# Connectors.net
KiCad netlist of a schematic drawn in Altium Designer
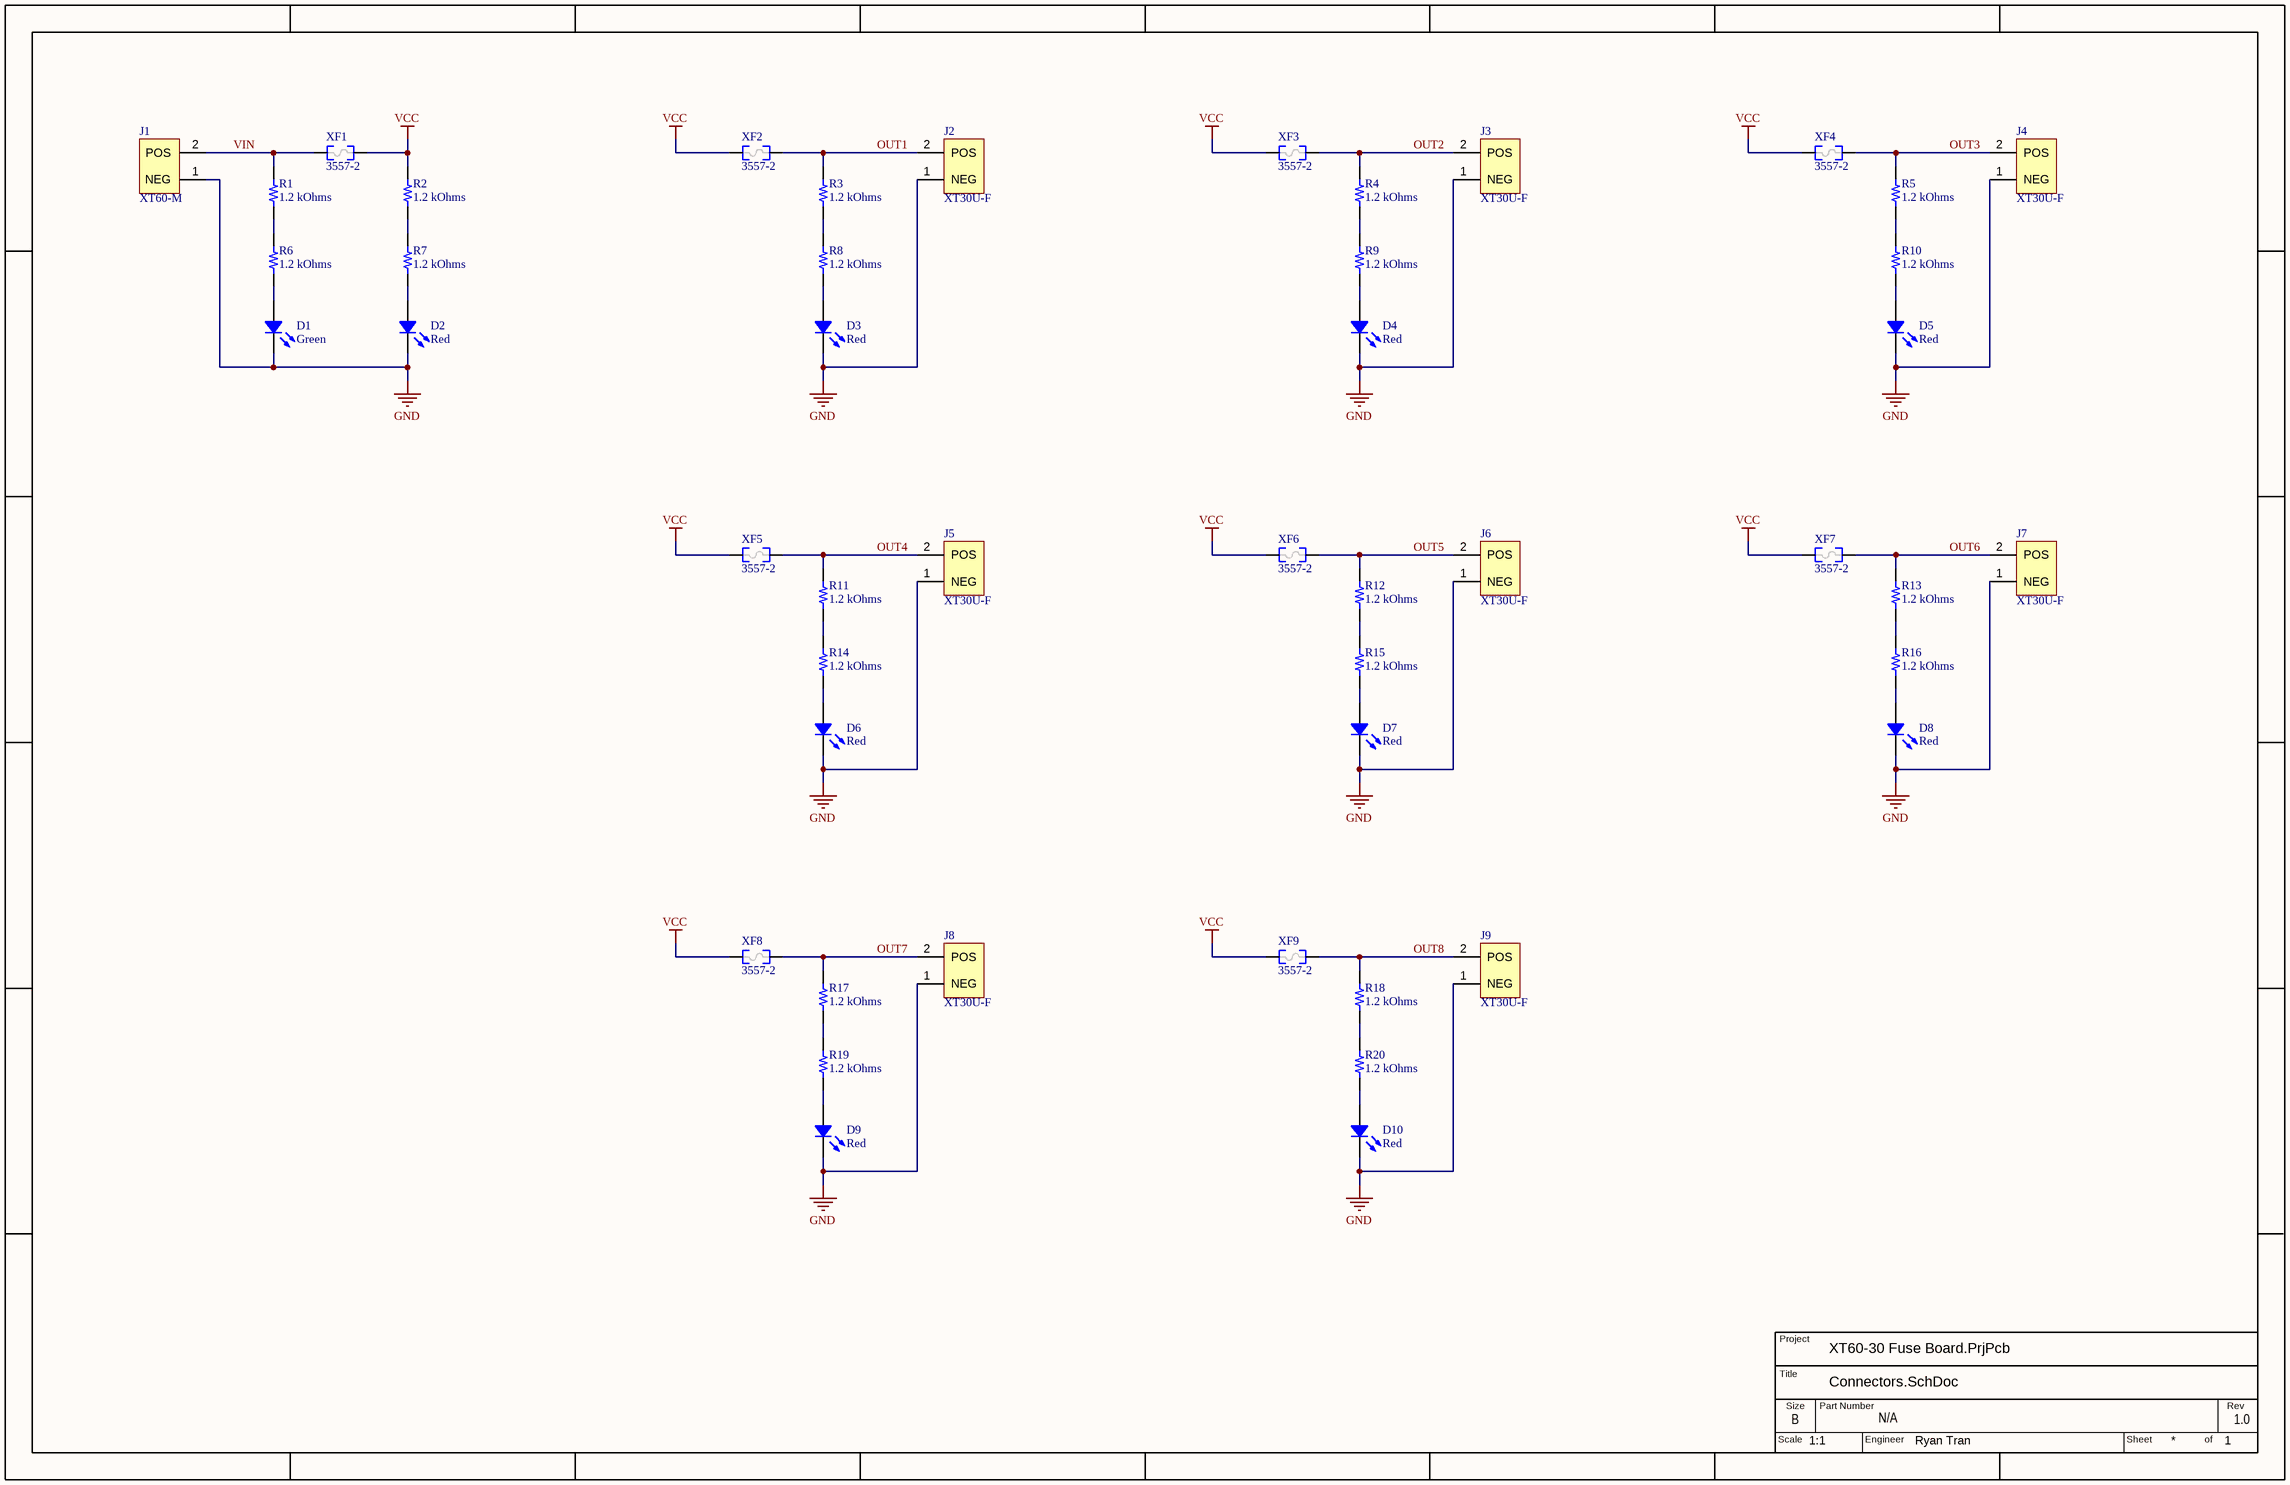
[diagram p0: Connectors.SchDoc]

(export (version "E")
  (design (tool "Eeschema 10.0.6"))
  (components
    (comp (ref "D1")
      (value "Green")
      (footprint "LED 0603_1608 GREEN")
      (description "LED GREEN CLEAR CHIP SMD")
      (fields (field (name "PART NUMBER") "LTST-C193TGKT-5A") (field (name "MANUFACTURER") "Lite-On Inc."))
      (libsource (lib "Celestial Altium Library - altium_library") (part "LED"))
    )
    (comp (ref "D2")
      (value "Red")
      (footprint "LED 0603_1608 RED")
      (description "LED RED CLEAR 2SMD")
      (fields
        (field (name "PART NUMBER") "19-217/R6C-AL1M2VY/3T")
        (field (name "MANUFACTURER") "Everlight Electronics Co Ltd")
      )
      (libsource (lib "Celestial Altium Library - altium_library") (part "LED"))
    )
    (comp (ref "D3")
      (value "Red")
      (footprint "LED 0603_1608 RED")
      (description "LED RED CLEAR 2SMD")
      (fields
        (field (name "PART NUMBER") "19-217/R6C-AL1M2VY/3T")
        (field (name "MANUFACTURER") "Everlight Electronics Co Ltd")
      )
      (libsource (lib "Celestial Altium Library - altium_library") (part "LED"))
    )
    (comp (ref "D4")
      (value "Red")
      (footprint "LED 0603_1608 RED")
      (description "LED RED CLEAR 2SMD")
      (fields
        (field (name "PART NUMBER") "19-217/R6C-AL1M2VY/3T")
        (field (name "MANUFACTURER") "Everlight Electronics Co Ltd")
      )
      (libsource (lib "Celestial Altium Library - altium_library") (part "LED"))
    )
    (comp (ref "D5")
      (value "Red")
      (footprint "LED 0603_1608 RED")
      (description "LED RED CLEAR 2SMD")
      (fields
        (field (name "PART NUMBER") "19-217/R6C-AL1M2VY/3T")
        (field (name "MANUFACTURER") "Everlight Electronics Co Ltd")
      )
      (libsource (lib "Celestial Altium Library - altium_library") (part "LED"))
    )
    (comp (ref "D6")
      (value "Red")
      (footprint "LED 0603_1608 RED")
      (description "LED RED CLEAR 2SMD")
      (fields
        (field (name "PART NUMBER") "19-217/R6C-AL1M2VY/3T")
        (field (name "MANUFACTURER") "Everlight Electronics Co Ltd")
      )
      (libsource (lib "Celestial Altium Library - altium_library") (part "LED"))
    )
    (comp (ref "D7")
      (value "Red")
      (footprint "LED 0603_1608 RED")
      (description "LED RED CLEAR 2SMD")
      (fields
        (field (name "PART NUMBER") "19-217/R6C-AL1M2VY/3T")
        (field (name "MANUFACTURER") "Everlight Electronics Co Ltd")
      )
      (libsource (lib "Celestial Altium Library - altium_library") (part "LED"))
    )
    (comp (ref "D8")
      (value "Red")
      (footprint "LED 0603_1608 RED")
      (description "LED RED CLEAR 2SMD")
      (fields
        (field (name "PART NUMBER") "19-217/R6C-AL1M2VY/3T")
        (field (name "MANUFACTURER") "Everlight Electronics Co Ltd")
      )
      (libsource (lib "Celestial Altium Library - altium_library") (part "LED"))
    )
    (comp (ref "D9")
      (value "Red")
      (footprint "LED 0603_1608 RED")
      (description "LED RED CLEAR 2SMD")
      (fields
        (field (name "PART NUMBER") "19-217/R6C-AL1M2VY/3T")
        (field (name "MANUFACTURER") "Everlight Electronics Co Ltd")
      )
      (libsource (lib "Celestial Altium Library - altium_library") (part "LED"))
    )
    (comp (ref "D10")
      (value "Red")
      (footprint "LED 0603_1608 RED")
      (description "LED RED CLEAR 2SMD")
      (fields
        (field (name "PART NUMBER") "19-217/R6C-AL1M2VY/3T")
        (field (name "MANUFACTURER") "Everlight Electronics Co Ltd")
      )
      (libsource (lib "Celestial Altium Library - altium_library") (part "LED"))
    )
    (comp (ref "J1")
      (value "XT60-M")
      (footprint "AMASS_XT60-M")
      (description "Plug; DC supply; XT60; male; PIN: 2; for cable; soldered; 30A; 500V")
      (fields (field (name "MF") "AMASS"))
      (libsource (lib "XT60-30_Fuse_Board_Symbols") (part "XT60-M"))
    )
    (comp (ref "J2")
      (value "XT30U-F")
      (footprint "AMASS_XT30-M")
      (description "Plug; DC supply; XT30; female; PIN: 2; for cable; soldering; 15A")
      (fields (field (name "MP") "XT60-M") (field (name "MF") "AMASS"))
      (libsource (lib "XT60-30_Fuse_Board_Symbols") (part "XT30U-F"))
    )
    (comp (ref "J3")
      (value "XT30U-F")
      (footprint "AMASS_XT30-M")
      (description "Plug; DC supply; XT30; female; PIN: 2; for cable; soldering; 15A")
      (fields (field (name "MP") "XT60-M") (field (name "MF") "AMASS"))
      (libsource (lib "XT60-30_Fuse_Board_Symbols") (part "XT30U-F"))
    )
    (comp (ref "J4")
      (value "XT30U-F")
      (footprint "AMASS_XT30-M")
      (description "Plug; DC supply; XT30; female; PIN: 2; for cable; soldering; 15A")
      (fields (field (name "MP") "XT60-M") (field (name "MF") "AMASS"))
      (libsource (lib "XT60-30_Fuse_Board_Symbols") (part "XT30U-F"))
    )
    (comp (ref "J5")
      (value "XT30U-F")
      (footprint "AMASS_XT30-M")
      (description "Plug; DC supply; XT30; female; PIN: 2; for cable; soldering; 15A")
      (fields (field (name "MP") "XT60-M") (field (name "MF") "AMASS"))
      (libsource (lib "XT60-30_Fuse_Board_Symbols") (part "XT30U-F"))
    )
    (comp (ref "J6")
      (value "XT30U-F")
      (footprint "AMASS_XT30-M")
      (description "Plug; DC supply; XT30; female; PIN: 2; for cable; soldering; 15A")
      (fields (field (name "MP") "XT60-M") (field (name "MF") "AMASS"))
      (libsource (lib "XT60-30_Fuse_Board_Symbols") (part "XT30U-F"))
    )
    (comp (ref "J7")
      (value "XT30U-F")
      (footprint "AMASS_XT30-M")
      (description "Plug; DC supply; XT30; female; PIN: 2; for cable; soldering; 15A")
      (fields (field (name "MP") "XT60-M") (field (name "MF") "AMASS"))
      (libsource (lib "XT60-30_Fuse_Board_Symbols") (part "XT30U-F"))
    )
    (comp (ref "J8")
      (value "XT30U-F")
      (footprint "AMASS_XT30-M")
      (description "Plug; DC supply; XT30; female; PIN: 2; for cable; soldering; 15A")
      (fields (field (name "MP") "XT60-M") (field (name "MF") "AMASS"))
      (libsource (lib "XT60-30_Fuse_Board_Symbols") (part "XT30U-F"))
    )
    (comp (ref "J9")
      (value "XT30U-F")
      (footprint "AMASS_XT30-M")
      (description "Plug; DC supply; XT30; female; PIN: 2; for cable; soldering; 15A")
      (fields (field (name "MP") "XT60-M") (field (name "MF") "AMASS"))
      (libsource (lib "XT60-30_Fuse_Board_Symbols") (part "XT30U-F"))
    )
    (comp (ref "R1")
      (value "1.2 kOhms")
      (footprint "RES 1210_3225")
      (description "RES SMD 1.2K OHM 5% 1/2W 1210")
      (fields
        (field (name "PART NUMBER") "ERJ-14YJ122U")
        (field (name "MANUFACTURER") "Panasonic Electronic Components")
      )
      (libsource (lib "Celestial Altium Library - altium_library") (part "Resistor"))
    )
    (comp (ref "R2")
      (value "1.2 kOhms")
      (footprint "RES 1210_3225")
      (description "RES SMD 1.2K OHM 5% 1/2W 1210")
      (fields
        (field (name "PART NUMBER") "ERJ-14YJ122U")
        (field (name "MANUFACTURER") "Panasonic Electronic Components")
      )
      (libsource (lib "Celestial Altium Library - altium_library") (part "Resistor"))
    )
    (comp (ref "R3")
      (value "1.2 kOhms")
      (footprint "RES 1210_3225")
      (description "RES SMD 1.2K OHM 5% 1/2W 1210")
      (fields
        (field (name "PART NUMBER") "ERJ-14YJ122U")
        (field (name "MANUFACTURER") "Panasonic Electronic Components")
      )
      (libsource (lib "Celestial Altium Library - altium_library") (part "Resistor"))
    )
    (comp (ref "R4")
      (value "1.2 kOhms")
      (footprint "RES 1210_3225")
      (description "RES SMD 1.2K OHM 5% 1/2W 1210")
      (fields
        (field (name "PART NUMBER") "ERJ-14YJ122U")
        (field (name "MANUFACTURER") "Panasonic Electronic Components")
      )
      (libsource (lib "Celestial Altium Library - altium_library") (part "Resistor"))
    )
    (comp (ref "R5")
      (value "1.2 kOhms")
      (footprint "RES 1210_3225")
      (description "RES SMD 1.2K OHM 5% 1/2W 1210")
      (fields
        (field (name "PART NUMBER") "ERJ-14YJ122U")
        (field (name "MANUFACTURER") "Panasonic Electronic Components")
      )
      (libsource (lib "Celestial Altium Library - altium_library") (part "Resistor"))
    )
    (comp (ref "R6")
      (value "1.2 kOhms")
      (footprint "RES 1210_3225")
      (description "RES SMD 1.2K OHM 5% 1/2W 1210")
      (fields
        (field (name "PART NUMBER") "ERJ-14YJ122U")
        (field (name "MANUFACTURER") "Panasonic Electronic Components")
      )
      (libsource (lib "Celestial Altium Library - altium_library") (part "Resistor"))
    )
    (comp (ref "R7")
      (value "1.2 kOhms")
      (footprint "RES 1210_3225")
      (description "RES SMD 1.2K OHM 5% 1/2W 1210")
      (fields
        (field (name "PART NUMBER") "ERJ-14YJ122U")
        (field (name "MANUFACTURER") "Panasonic Electronic Components")
      )
      (libsource (lib "Celestial Altium Library - altium_library") (part "Resistor"))
    )
    (comp (ref "R8")
      (value "1.2 kOhms")
      (footprint "RES 1210_3225")
      (description "RES SMD 1.2K OHM 5% 1/2W 1210")
      (fields
        (field (name "PART NUMBER") "ERJ-14YJ122U")
        (field (name "MANUFACTURER") "Panasonic Electronic Components")
      )
      (libsource (lib "Celestial Altium Library - altium_library") (part "Resistor"))
    )
    (comp (ref "R9")
      (value "1.2 kOhms")
      (footprint "RES 1210_3225")
      (description "RES SMD 1.2K OHM 5% 1/2W 1210")
      (fields
        (field (name "PART NUMBER") "ERJ-14YJ122U")
        (field (name "MANUFACTURER") "Panasonic Electronic Components")
      )
      (libsource (lib "Celestial Altium Library - altium_library") (part "Resistor"))
    )
    (comp (ref "R10")
      (value "1.2 kOhms")
      (footprint "RES 1210_3225")
      (description "RES SMD 1.2K OHM 5% 1/2W 1210")
      (fields
        (field (name "PART NUMBER") "ERJ-14YJ122U")
        (field (name "MANUFACTURER") "Panasonic Electronic Components")
      )
      (libsource (lib "Celestial Altium Library - altium_library") (part "Resistor"))
    )
    (comp (ref "R11")
      (value "1.2 kOhms")
      (footprint "RES 1210_3225")
      (description "RES SMD 1.2K OHM 5% 1/2W 1210")
      (fields
        (field (name "PART NUMBER") "ERJ-14YJ122U")
        (field (name "MANUFACTURER") "Panasonic Electronic Components")
      )
      (libsource (lib "Celestial Altium Library - altium_library") (part "Resistor"))
    )
    (comp (ref "R12")
      (value "1.2 kOhms")
      (footprint "RES 1210_3225")
      (description "RES SMD 1.2K OHM 5% 1/2W 1210")
      (fields
        (field (name "PART NUMBER") "ERJ-14YJ122U")
        (field (name "MANUFACTURER") "Panasonic Electronic Components")
      )
      (libsource (lib "Celestial Altium Library - altium_library") (part "Resistor"))
    )
    (comp (ref "R13")
      (value "1.2 kOhms")
      (footprint "RES 1210_3225")
      (description "RES SMD 1.2K OHM 5% 1/2W 1210")
      (fields
        (field (name "PART NUMBER") "ERJ-14YJ122U")
        (field (name "MANUFACTURER") "Panasonic Electronic Components")
      )
      (libsource (lib "Celestial Altium Library - altium_library") (part "Resistor"))
    )
    (comp (ref "R14")
      (value "1.2 kOhms")
      (footprint "RES 1210_3225")
      (description "RES SMD 1.2K OHM 5% 1/2W 1210")
      (fields
        (field (name "PART NUMBER") "ERJ-14YJ122U")
        (field (name "MANUFACTURER") "Panasonic Electronic Components")
      )
      (libsource (lib "Celestial Altium Library - altium_library") (part "Resistor"))
    )
    (comp (ref "R15")
      (value "1.2 kOhms")
      (footprint "RES 1210_3225")
      (description "RES SMD 1.2K OHM 5% 1/2W 1210")
      (fields
        (field (name "PART NUMBER") "ERJ-14YJ122U")
        (field (name "MANUFACTURER") "Panasonic Electronic Components")
      )
      (libsource (lib "Celestial Altium Library - altium_library") (part "Resistor"))
    )
    (comp (ref "R16")
      (value "1.2 kOhms")
      (footprint "RES 1210_3225")
      (description "RES SMD 1.2K OHM 5% 1/2W 1210")
      (fields
        (field (name "PART NUMBER") "ERJ-14YJ122U")
        (field (name "MANUFACTURER") "Panasonic Electronic Components")
      )
      (libsource (lib "Celestial Altium Library - altium_library") (part "Resistor"))
    )
    (comp (ref "R17")
      (value "1.2 kOhms")
      (footprint "RES 1210_3225")
      (description "RES SMD 1.2K OHM 5% 1/2W 1210")
      (fields
        (field (name "PART NUMBER") "ERJ-14YJ122U")
        (field (name "MANUFACTURER") "Panasonic Electronic Components")
      )
      (libsource (lib "Celestial Altium Library - altium_library") (part "Resistor"))
    )
    (comp (ref "R18")
      (value "1.2 kOhms")
      (footprint "RES 1210_3225")
      (description "RES SMD 1.2K OHM 5% 1/2W 1210")
      (fields
        (field (name "PART NUMBER") "ERJ-14YJ122U")
        (field (name "MANUFACTURER") "Panasonic Electronic Components")
      )
      (libsource (lib "Celestial Altium Library - altium_library") (part "Resistor"))
    )
    (comp (ref "R19")
      (value "1.2 kOhms")
      (footprint "RES 1210_3225")
      (description "RES SMD 1.2K OHM 5% 1/2W 1210")
      (fields
        (field (name "PART NUMBER") "ERJ-14YJ122U")
        (field (name "MANUFACTURER") "Panasonic Electronic Components")
      )
      (libsource (lib "Celestial Altium Library - altium_library") (part "Resistor"))
    )
    (comp (ref "R20")
      (value "1.2 kOhms")
      (footprint "RES 1210_3225")
      (description "RES SMD 1.2K OHM 5% 1/2W 1210")
      (fields
        (field (name "PART NUMBER") "ERJ-14YJ122U")
        (field (name "MANUFACTURER") "Panasonic Electronic Components")
      )
      (libsource (lib "Celestial Altium Library - altium_library") (part "Resistor"))
    )
    (comp (ref "XF1")
      (value "3557-2")
      (footprint "FUSE_3557-2")
      (description "Fuse Block 30A 500V 1 Circuit Blade Through Hole")
      (fields (field (name "MF") "Keystone Electronics"))
      (libsource (lib "XT60-30_Fuse_Board_Symbols") (part "3557-2"))
    )
    (comp (ref "XF2")
      (value "3557-2")
      (footprint "FUSE_3557-2")
      (description "Fuse Block 30A 500V 1 Circuit Blade Through Hole")
      (fields (field (name "MF") "Keystone Electronics"))
      (libsource (lib "XT60-30_Fuse_Board_Symbols") (part "3557-2"))
    )
    (comp (ref "XF3")
      (value "3557-2")
      (footprint "FUSE_3557-2")
      (description "Fuse Block 30A 500V 1 Circuit Blade Through Hole")
      (fields (field (name "MF") "Keystone Electronics"))
      (libsource (lib "XT60-30_Fuse_Board_Symbols") (part "3557-2"))
    )
    (comp (ref "XF4")
      (value "3557-2")
      (footprint "FUSE_3557-2")
      (description "Fuse Block 30A 500V 1 Circuit Blade Through Hole")
      (fields (field (name "MF") "Keystone Electronics"))
      (libsource (lib "XT60-30_Fuse_Board_Symbols") (part "3557-2"))
    )
    (comp (ref "XF5")
      (value "3557-2")
      (footprint "FUSE_3557-2")
      (description "Fuse Block 30A 500V 1 Circuit Blade Through Hole")
      (fields (field (name "MF") "Keystone Electronics"))
      (libsource (lib "XT60-30_Fuse_Board_Symbols") (part "3557-2"))
    )
    (comp (ref "XF6")
      (value "3557-2")
      (footprint "FUSE_3557-2")
      (description "Fuse Block 30A 500V 1 Circuit Blade Through Hole")
      (fields (field (name "MF") "Keystone Electronics"))
      (libsource (lib "XT60-30_Fuse_Board_Symbols") (part "3557-2"))
    )
    (comp (ref "XF7")
      (value "3557-2")
      (footprint "FUSE_3557-2")
      (description "Fuse Block 30A 500V 1 Circuit Blade Through Hole")
      (fields (field (name "MF") "Keystone Electronics"))
      (libsource (lib "XT60-30_Fuse_Board_Symbols") (part "3557-2"))
    )
    (comp (ref "XF8")
      (value "3557-2")
      (footprint "FUSE_3557-2")
      (description "Fuse Block 30A 500V 1 Circuit Blade Through Hole")
      (fields (field (name "MF") "Keystone Electronics"))
      (libsource (lib "XT60-30_Fuse_Board_Symbols") (part "3557-2"))
    )
    (comp (ref "XF9")
      (value "3557-2")
      (footprint "FUSE_3557-2")
      (description "Fuse Block 30A 500V 1 Circuit Blade Through Hole")
      (fields (field (name "MF") "Keystone Electronics"))
      (libsource (lib "XT60-30_Fuse_Board_Symbols") (part "3557-2"))
    )
  )
  (nets
    (net (code "1") (name "/OUT1") (class "Default")
      (node (ref "J2") (pin "2") (pinfunction "POS_2") (pintype "passive"))
      (node (ref "R3") (pin "2") (pinfunction "2_2") (pintype "passive"))
      (node (ref "XF2") (pin "2") (pinfunction "2_2") (pintype "passive"))
    )
    (net (code "2") (name "/OUT2") (class "Default")
      (node (ref "J3") (pin "2") (pinfunction "POS_2") (pintype "passive"))
      (node (ref "R4") (pin "2") (pinfunction "2_2") (pintype "passive"))
      (node (ref "XF3") (pin "2") (pinfunction "2_2") (pintype "passive"))
    )
    (net (code "3") (name "/OUT3") (class "Default")
      (node (ref "J4") (pin "2") (pinfunction "POS_2") (pintype "passive"))
      (node (ref "R5") (pin "2") (pinfunction "2_2") (pintype "passive"))
      (node (ref "XF4") (pin "2") (pinfunction "2_2") (pintype "passive"))
    )
    (net (code "4") (name "/OUT4") (class "Default")
      (node (ref "J5") (pin "2") (pinfunction "POS_2") (pintype "passive"))
      (node (ref "R11") (pin "2") (pinfunction "2_2") (pintype "passive"))
      (node (ref "XF5") (pin "2") (pinfunction "2_2") (pintype "passive"))
    )
    (net (code "5") (name "/OUT5") (class "Default")
      (node (ref "J6") (pin "2") (pinfunction "POS_2") (pintype "passive"))
      (node (ref "R12") (pin "2") (pinfunction "2_2") (pintype "passive"))
      (node (ref "XF6") (pin "2") (pinfunction "2_2") (pintype "passive"))
    )
    (net (code "6") (name "/OUT6") (class "Default")
      (node (ref "J7") (pin "2") (pinfunction "POS_2") (pintype "passive"))
      (node (ref "R13") (pin "2") (pinfunction "2_2") (pintype "passive"))
      (node (ref "XF7") (pin "2") (pinfunction "2_2") (pintype "passive"))
    )
    (net (code "7") (name "/OUT7") (class "Default")
      (node (ref "J8") (pin "2") (pinfunction "POS_2") (pintype "passive"))
      (node (ref "R17") (pin "2") (pinfunction "2_2") (pintype "passive"))
      (node (ref "XF8") (pin "2") (pinfunction "2_2") (pintype "passive"))
    )
    (net (code "8") (name "/OUT8") (class "Default")
      (node (ref "J9") (pin "2") (pinfunction "POS_2") (pintype "passive"))
      (node (ref "R18") (pin "2") (pinfunction "2_2") (pintype "passive"))
      (node (ref "XF9") (pin "2") (pinfunction "2_2") (pintype "passive"))
    )
    (net (code "9") (name "/VIN") (class "Default")
      (node (ref "J1") (pin "2") (pinfunction "POS_2") (pintype "passive"))
      (node (ref "R1") (pin "2") (pinfunction "2_2") (pintype "passive"))
      (node (ref "XF1") (pin "1") (pinfunction "1_1") (pintype "passive"))
    )
    (net (code "10") (name "GND") (class "Default")
      (node (ref "D1") (pin "2") (pinfunction "2_2") (pintype "passive"))
      (node (ref "D10") (pin "2") (pinfunction "2_2") (pintype "passive"))
      (node (ref "D2") (pin "2") (pinfunction "2_2") (pintype "passive"))
      (node (ref "D3") (pin "2") (pinfunction "2_2") (pintype "passive"))
      (node (ref "D4") (pin "2") (pinfunction "2_2") (pintype "passive"))
      (node (ref "D5") (pin "2") (pinfunction "2_2") (pintype "passive"))
      (node (ref "D6") (pin "2") (pinfunction "2_2") (pintype "passive"))
      (node (ref "D7") (pin "2") (pinfunction "2_2") (pintype "passive"))
      (node (ref "D8") (pin "2") (pinfunction "2_2") (pintype "passive"))
      (node (ref "D9") (pin "2") (pinfunction "2_2") (pintype "passive"))
      (node (ref "J1") (pin "1") (pinfunction "NEG_1") (pintype "passive"))
      (node (ref "J2") (pin "1") (pinfunction "NEG_1") (pintype "passive"))
      (node (ref "J3") (pin "1") (pinfunction "NEG_1") (pintype "passive"))
      (node (ref "J4") (pin "1") (pinfunction "NEG_1") (pintype "passive"))
      (node (ref "J5") (pin "1") (pinfunction "NEG_1") (pintype "passive"))
      (node (ref "J6") (pin "1") (pinfunction "NEG_1") (pintype "passive"))
      (node (ref "J7") (pin "1") (pinfunction "NEG_1") (pintype "passive"))
      (node (ref "J8") (pin "1") (pinfunction "NEG_1") (pintype "passive"))
      (node (ref "J9") (pin "1") (pinfunction "NEG_1") (pintype "passive"))
    )
    (net (code "11") (name "Net-(D1-Pad1)") (class "Default")
      (node (ref "D1") (pin "1") (pinfunction "1_1") (pintype "passive"))
      (node (ref "R6") (pin "1") (pinfunction "1_1") (pintype "passive"))
    )
    (net (code "12") (name "Net-(D2-Pad1)") (class "Default")
      (node (ref "D2") (pin "1") (pinfunction "1_1") (pintype "passive"))
      (node (ref "R7") (pin "1") (pinfunction "1_1") (pintype "passive"))
    )
    (net (code "13") (name "Net-(D3-Pad1)") (class "Default")
      (node (ref "D3") (pin "1") (pinfunction "1_1") (pintype "passive"))
      (node (ref "R8") (pin "1") (pinfunction "1_1") (pintype "passive"))
    )
    (net (code "14") (name "Net-(D4-Pad1)") (class "Default")
      (node (ref "D4") (pin "1") (pinfunction "1_1") (pintype "passive"))
      (node (ref "R9") (pin "1") (pinfunction "1_1") (pintype "passive"))
    )
    (net (code "15") (name "Net-(D5-Pad1)") (class "Default")
      (node (ref "D5") (pin "1") (pinfunction "1_1") (pintype "passive"))
      (node (ref "R10") (pin "1") (pinfunction "1_1") (pintype "passive"))
    )
    (net (code "16") (name "Net-(D6-Pad1)") (class "Default")
      (node (ref "D6") (pin "1") (pinfunction "1_1") (pintype "passive"))
      (node (ref "R14") (pin "1") (pinfunction "1_1") (pintype "passive"))
    )
    (net (code "17") (name "Net-(D7-Pad1)") (class "Default")
      (node (ref "D7") (pin "1") (pinfunction "1_1") (pintype "passive"))
      (node (ref "R15") (pin "1") (pinfunction "1_1") (pintype "passive"))
    )
    (net (code "18") (name "Net-(D8-Pad1)") (class "Default")
      (node (ref "D8") (pin "1") (pinfunction "1_1") (pintype "passive"))
      (node (ref "R16") (pin "1") (pinfunction "1_1") (pintype "passive"))
    )
    (net (code "19") (name "Net-(D9-Pad1)") (class "Default")
      (node (ref "D9") (pin "1") (pinfunction "1_1") (pintype "passive"))
      (node (ref "R19") (pin "1") (pinfunction "1_1") (pintype "passive"))
    )
    (net (code "20") (name "Net-(D10-Pad1)") (class "Default")
      (node (ref "D10") (pin "1") (pinfunction "1_1") (pintype "passive"))
      (node (ref "R20") (pin "1") (pinfunction "1_1") (pintype "passive"))
    )
    (net (code "21") (name "Net-(R1-Pad1)") (class "Default")
      (node (ref "R1") (pin "1") (pinfunction "1_1") (pintype "passive"))
      (node (ref "R6") (pin "2") (pinfunction "2_2") (pintype "passive"))
    )
    (net (code "22") (name "Net-(R2-Pad1)") (class "Default")
      (node (ref "R2") (pin "1") (pinfunction "1_1") (pintype "passive"))
      (node (ref "R7") (pin "2") (pinfunction "2_2") (pintype "passive"))
    )
    (net (code "23") (name "Net-(R3-Pad1)") (class "Default")
      (node (ref "R3") (pin "1") (pinfunction "1_1") (pintype "passive"))
      (node (ref "R8") (pin "2") (pinfunction "2_2") (pintype "passive"))
    )
    (net (code "24") (name "Net-(R4-Pad1)") (class "Default")
      (node (ref "R4") (pin "1") (pinfunction "1_1") (pintype "passive"))
      (node (ref "R9") (pin "2") (pinfunction "2_2") (pintype "passive"))
    )
    (net (code "25") (name "Net-(R10-Pad2)") (class "Default")
      (node (ref "R10") (pin "2") (pinfunction "2_2") (pintype "passive"))
      (node (ref "R5") (pin "1") (pinfunction "1_1") (pintype "passive"))
    )
    (net (code "26") (name "Net-(R11-Pad1)") (class "Default")
      (node (ref "R11") (pin "1") (pinfunction "1_1") (pintype "passive"))
      (node (ref "R14") (pin "2") (pinfunction "2_2") (pintype "passive"))
    )
    (net (code "27") (name "Net-(R12-Pad1)") (class "Default")
      (node (ref "R12") (pin "1") (pinfunction "1_1") (pintype "passive"))
      (node (ref "R15") (pin "2") (pinfunction "2_2") (pintype "passive"))
    )
    (net (code "28") (name "Net-(R13-Pad1)") (class "Default")
      (node (ref "R13") (pin "1") (pinfunction "1_1") (pintype "passive"))
      (node (ref "R16") (pin "2") (pinfunction "2_2") (pintype "passive"))
    )
    (net (code "29") (name "Net-(R17-Pad1)") (class "Default")
      (node (ref "R17") (pin "1") (pinfunction "1_1") (pintype "passive"))
      (node (ref "R19") (pin "2") (pinfunction "2_2") (pintype "passive"))
    )
    (net (code "30") (name "Net-(R18-Pad1)") (class "Default")
      (node (ref "R18") (pin "1") (pinfunction "1_1") (pintype "passive"))
      (node (ref "R20") (pin "2") (pinfunction "2_2") (pintype "passive"))
    )
    (net (code "31") (name "VCC") (class "Default")
      (node (ref "R2") (pin "2") (pinfunction "2_2") (pintype "passive"))
      (node (ref "XF1") (pin "2") (pinfunction "2_2") (pintype "passive"))
      (node (ref "XF2") (pin "1") (pinfunction "1_1") (pintype "passive"))
      (node (ref "XF3") (pin "1") (pinfunction "1_1") (pintype "passive"))
      (node (ref "XF4") (pin "1") (pinfunction "1_1") (pintype "passive"))
      (node (ref "XF5") (pin "1") (pinfunction "1_1") (pintype "passive"))
      (node (ref "XF6") (pin "1") (pinfunction "1_1") (pintype "passive"))
      (node (ref "XF7") (pin "1") (pinfunction "1_1") (pintype "passive"))
      (node (ref "XF8") (pin "1") (pinfunction "1_1") (pintype "passive"))
      (node (ref "XF9") (pin "1") (pinfunction "1_1") (pintype "passive"))
    )
  )
)
